# Sheet2.net
KiCad netlist of a schematic drawn in Altium Designer
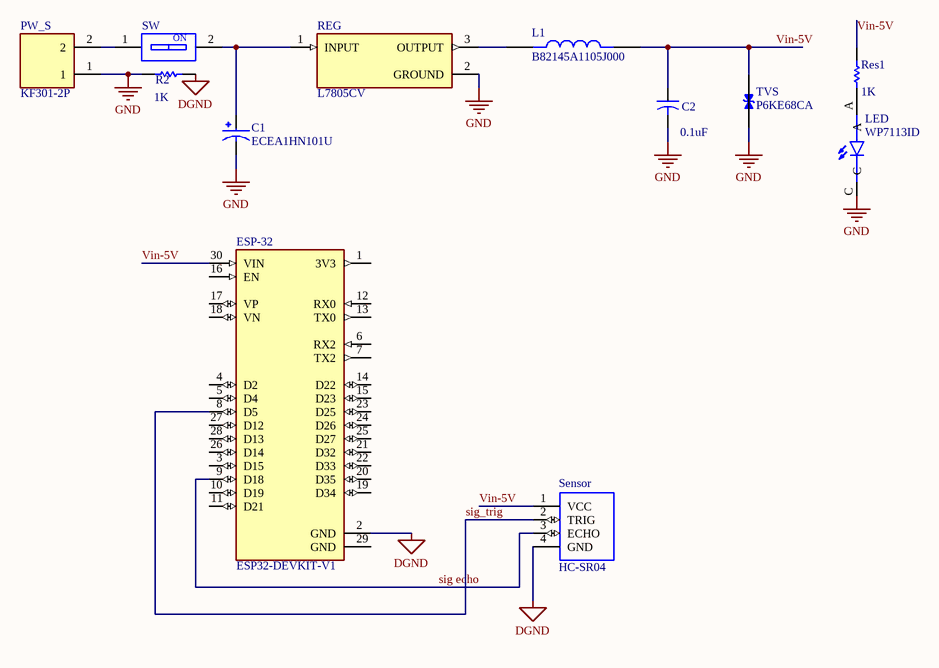
[diagram p0: Sheet2.SchDoc]

(export (version "E")
  (design (tool "Eeschema 10.0.6"))
  (components
    (comp (ref "C1")
      (value "ECEA1HN101U")
      (footprint "CAPPRD500W60D1000H2000")
      (description "Capacitor [Panasonic Automotive & Industrial Systems] ECEA1HN101U Capacitor")
      (fields (field (name "MF") "Panasonic"))
      (libsource (lib "ECEA1HN101U") (part "ECEA1HN101U"))
    )
    (comp (ref "C2")
      (value "0.1uF")
      (footprint "CAPR5-4X5")
      (description "Capacitor")
      (fields (field (name "Comment") "Cap2") (field (name "PUBLISHER") "Altium Limited"))
      (libsource (lib "Miscellaneous+Devices") (part "Cap2"))
    )
    (comp (ref "ESP-32")
      (value "ESP32-DEVKIT-V1")
      (footprint "MODULE_ESP32_DEVKIT_V1")
      (fields (field (name "MF") "Do it"))
      (libsource (lib "ESP32-DEVKIT-V1 (1)") (part "ESP32-DEVKIT-V1"))
    )
    (comp (ref "L1")
      (value "B82145A1105J000")
      (footprint "INDAD1680W80L1200D650")
      (description "FIXED IND 1MH 370MA 3.6 OHM TH")
      (fields (field (name "MF") "TDK"))
      (libsource (lib "B82145A1105J000") (part "B82145A1105J000"))
    )
    (comp (ref "LED")
      (value "WP7113ID")
      (footprint "LED_WP7113ID")
      (description "Red 617nm LED Indication - Discrete 2V Radial")
      (fields (field (name "MF") "Kingbright"))
      (libsource (lib "WP7113ID") (part "WP7113ID"))
    )
    (comp (ref "PW_S")
      (value "KF301-2P")
      (footprint "HANDSON_KF301-2P")
      (description "2 Pin Terminal Block 5mm Pitch")
      (fields (field (name "MF") "Handson Technology"))
      (libsource (lib "KF301-2P") (part "KF301-2P"))
    )
    (comp (ref "R2")
      (value "1K")
      (footprint "AXIAL-0.3")
      (description "Resistor")
      (fields (field (name "Comment") "Res1") (field (name "PUBLISHER") "Altium Limited"))
      (libsource (lib "Miscellaneous+Devices") (part "Res1"))
    )
    (comp (ref "REG")
      (value "L7805CV")
      (footprint "TO255P1040X460X1968-3")
      (description "Linear Voltage Regulator IC Positive Fixed 1 Output 1.5A TO-220")
      (fields (field (name "MF") "STMicroelectronics"))
      (libsource (lib "L7805CV") (part "L7805CV"))
    )
    (comp (ref "Res1")
      (value "1K")
      (footprint "AXIAL-0.3")
      (description "Resistor")
      (fields (field (name "Comment") "Res1") (field (name "PUBLISHER") "Altium Limited"))
      (libsource (lib "Miscellaneous+Devices") (part "Res1"))
    )
    (comp (ref "Sensor")
      (value "HC-SR04")
      (footprint "XCVR_HC-SR04")
      (description "Ultrasonic Sensor Module")
      (libsource (lib "HC-SR04") (part "HC-SR04"))
    )
    (comp (ref "SW")
      (value "418117170901")
      (footprint "418117170901")
      (description "WS-DITV Compact THT Dip Switch, Flat Actuator, pitch 2.54mm, 1p")
      (fields (field (name "MANUFACTURER") "Wurth Elektronik"))
      (libsource (lib "Altium_WS-DITV+(rev22a)") (part "418117170901"))
    )
    (comp (ref "TVS")
      (value "P6KE68CA")
      (footprint "DIOAD1300W80L670D310")
      (libsource (lib "P6KE68CA") (part "P6KE68CA"))
    )
  )
  (nets
    (net (code "1") (name "/Vin-5V") (class "Default")
      (node (ref "C2") (pin "1") (pinfunction "1_1") (pintype "passive"))
      (node (ref "ESP-32") (pin "30") (pinfunction "VIN_30") (pintype "input"))
      (node (ref "L1") (pin "2") (pinfunction "2_2") (pintype "passive"))
      (node (ref "Res1") (pin "1") (pinfunction "1_1") (pintype "passive"))
      (node (ref "Sensor") (pin "1") (pinfunction "VCC_1") (pintype "power_in"))
      (node (ref "TVS") (pin "2") (pinfunction "2_2") (pintype "passive"))
    )
    (net (code "2") (name "/sig echo") (class "Default")
      (node (ref "ESP-32") (pin "9") (pinfunction "D18_9") (pintype "bidirectional"))
      (node (ref "Sensor") (pin "3") (pinfunction "ECHO_3") (pintype "bidirectional"))
    )
    (net (code "3") (name "/sig_trig") (class "Default")
      (node (ref "ESP-32") (pin "8") (pinfunction "D5_8") (pintype "bidirectional"))
      (node (ref "Sensor") (pin "2") (pinfunction "TRIG_2") (pintype "bidirectional"))
    )
    (net (code "4") (name "DGND") (class "Default")
      (node (ref "ESP-32") (pin "2") (pinfunction "GND_2") (pintype "power_in"))
      (node (ref "R2") (pin "2") (pinfunction "2_2") (pintype "passive"))
      (node (ref "Sensor") (pin "4") (pinfunction "GND_4") (pintype "power_in"))
    )
    (net (code "5") (name "GND") (class "Default")
      (node (ref "C1") (pin "N") (pinfunction "N_N") (pintype "passive"))
      (node (ref "C2") (pin "2") (pinfunction "2_2") (pintype "passive"))
      (node (ref "LED") (pin "C") (pinfunction "C_C") (pintype "passive"))
      (node (ref "PW_S") (pin "1") (pinfunction "1_1") (pintype "passive"))
      (node (ref "R2") (pin "1") (pinfunction "1_1") (pintype "passive"))
      (node (ref "REG") (pin "2") (pinfunction "GROUND_2") (pintype "power_in"))
      (node (ref "TVS") (pin "1") (pinfunction "1_1") (pintype "passive"))
    )
    (net (code "6") (name "Net-(LED-PadA)") (class "Default")
      (node (ref "LED") (pin "A") (pinfunction "A_A") (pintype "passive"))
      (node (ref "Res1") (pin "2") (pinfunction "2_2") (pintype "passive"))
    )
    (net (code "7") (name "Net-(PW_S-Pad2)") (class "Default")
      (node (ref "PW_S") (pin "2") (pinfunction "2_2") (pintype "passive"))
      (node (ref "SW") (pin "1") (pinfunction "1_1") (pintype "passive"))
    )
    (net (code "8") (name "Net-(REG-INPUT)") (class "Default")
      (node (ref "C1") (pin "P") (pinfunction "P_P") (pintype "passive"))
      (node (ref "REG") (pin "1") (pinfunction "INPUT_1") (pintype "input"))
      (node (ref "SW") (pin "2") (pinfunction "2_2") (pintype "passive"))
    )
    (net (code "9") (name "Net-(REG-OUTPUT)") (class "Default")
      (node (ref "L1") (pin "1") (pinfunction "1_1") (pintype "passive"))
      (node (ref "REG") (pin "3") (pinfunction "OUTPUT_3") (pintype "output"))
    )
    (net (code "10") (name "unconnected-(ESP-32-3V3-Pad1)") (class "Default")
      (node (ref "ESP-32") (pin "1") (pinfunction "3V3_1") (pintype "output"))
    )
    (net (code "11") (name "unconnected-(ESP-32-D2-Pad4)") (class "Default")
      (node (ref "ESP-32") (pin "4") (pinfunction "D2_4") (pintype "bidirectional"))
    )
    (net (code "12") (name "unconnected-(ESP-32-D4-Pad5)") (class "Default")
      (node (ref "ESP-32") (pin "5") (pinfunction "D4_5") (pintype "bidirectional"))
    )
    (net (code "13") (name "unconnected-(ESP-32-D12-Pad27)") (class "Default")
      (node (ref "ESP-32") (pin "27") (pinfunction "D12_27") (pintype "bidirectional"))
    )
    (net (code "14") (name "unconnected-(ESP-32-D13-Pad28)") (class "Default")
      (node (ref "ESP-32") (pin "28") (pinfunction "D13_28") (pintype "bidirectional"))
    )
    (net (code "15") (name "unconnected-(ESP-32-D14-Pad26)") (class "Default")
      (node (ref "ESP-32") (pin "26") (pinfunction "D14_26") (pintype "bidirectional"))
    )
    (net (code "16") (name "unconnected-(ESP-32-D15-Pad3)") (class "Default")
      (node (ref "ESP-32") (pin "3") (pinfunction "D15_3") (pintype "bidirectional"))
    )
    (net (code "17") (name "unconnected-(ESP-32-D19-Pad10)") (class "Default")
      (node (ref "ESP-32") (pin "10") (pinfunction "D19_10") (pintype "bidirectional"))
    )
    (net (code "18") (name "unconnected-(ESP-32-D21-Pad11)") (class "Default")
      (node (ref "ESP-32") (pin "11") (pinfunction "D21_11") (pintype "bidirectional"))
    )
    (net (code "19") (name "unconnected-(ESP-32-D22-Pad14)") (class "Default")
      (node (ref "ESP-32") (pin "14") (pinfunction "D22_14") (pintype "bidirectional"))
    )
    (net (code "20") (name "unconnected-(ESP-32-D23-Pad15)") (class "Default")
      (node (ref "ESP-32") (pin "15") (pinfunction "D23_15") (pintype "bidirectional"))
    )
    (net (code "21") (name "unconnected-(ESP-32-D25-Pad23)") (class "Default")
      (node (ref "ESP-32") (pin "23") (pinfunction "D25_23") (pintype "bidirectional"))
    )
    (net (code "22") (name "unconnected-(ESP-32-D26-Pad24)") (class "Default")
      (node (ref "ESP-32") (pin "24") (pinfunction "D26_24") (pintype "bidirectional"))
    )
    (net (code "23") (name "unconnected-(ESP-32-D27-Pad25)") (class "Default")
      (node (ref "ESP-32") (pin "25") (pinfunction "D27_25") (pintype "bidirectional"))
    )
    (net (code "24") (name "unconnected-(ESP-32-D32-Pad21)") (class "Default")
      (node (ref "ESP-32") (pin "21") (pinfunction "D32_21") (pintype "bidirectional"))
    )
    (net (code "25") (name "unconnected-(ESP-32-D33-Pad22)") (class "Default")
      (node (ref "ESP-32") (pin "22") (pinfunction "D33_22") (pintype "bidirectional"))
    )
    (net (code "26") (name "unconnected-(ESP-32-D34-Pad19)") (class "Default")
      (node (ref "ESP-32") (pin "19") (pinfunction "D34_19") (pintype "bidirectional"))
    )
    (net (code "27") (name "unconnected-(ESP-32-D35-Pad20)") (class "Default")
      (node (ref "ESP-32") (pin "20") (pinfunction "D35_20") (pintype "bidirectional"))
    )
    (net (code "28") (name "unconnected-(ESP-32-EN-Pad16)") (class "Default")
      (node (ref "ESP-32") (pin "16") (pinfunction "EN_16") (pintype "input"))
    )
    (net (code "29") (name "unconnected-(ESP-32-GND-Pad29)") (class "Default")
      (node (ref "ESP-32") (pin "29") (pinfunction "GND_29") (pintype "power_in"))
    )
    (net (code "30") (name "unconnected-(ESP-32-RX0-Pad12)") (class "Default")
      (node (ref "ESP-32") (pin "12") (pinfunction "RX0_12") (pintype "input"))
    )
    (net (code "31") (name "unconnected-(ESP-32-RX2-Pad6)") (class "Default")
      (node (ref "ESP-32") (pin "6") (pinfunction "RX2_6") (pintype "input"))
    )
    (net (code "32") (name "unconnected-(ESP-32-TX0-Pad13)") (class "Default")
      (node (ref "ESP-32") (pin "13") (pinfunction "TX0_13") (pintype "output"))
    )
    (net (code "33") (name "unconnected-(ESP-32-TX2-Pad7)") (class "Default")
      (node (ref "ESP-32") (pin "7") (pinfunction "TX2_7") (pintype "output"))
    )
    (net (code "34") (name "unconnected-(ESP-32-VN-Pad18)") (class "Default")
      (node (ref "ESP-32") (pin "18") (pinfunction "VN_18") (pintype "bidirectional"))
    )
    (net (code "35") (name "unconnected-(ESP-32-VP-Pad17)") (class "Default")
      (node (ref "ESP-32") (pin "17") (pinfunction "VP_17") (pintype "bidirectional"))
    )
  )
)
